# usbmidi2cv.net
KiCad netlist of a schematic drawn in EAGLE
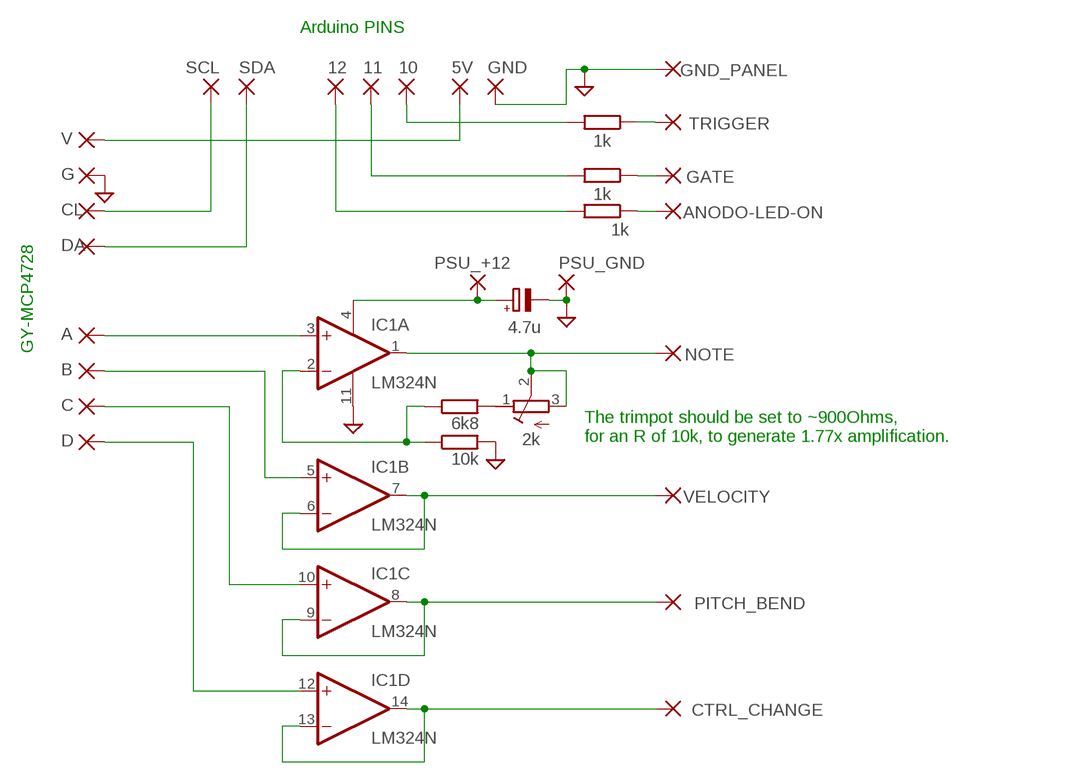
[diagram p0: schematic, sheet 1]

(export (version "E")
  (design (tool "Eeschema 10.0.6"))
  (components
    (comp (ref "5V")
      (value "1,6/0,8")
      (footprint "eagle-import:1,6_0,8")
      (libsource (lib "eagle-import") (part "1,6/0,8"))
    )
    (comp (ref "10")
      (value "1,6/0,8")
      (footprint "eagle-import:1,6_0,8")
      (libsource (lib "eagle-import") (part "1,6/0,8"))
    )
    (comp (ref "11")
      (value "1,6/0,8")
      (footprint "eagle-import:1,6_0,8")
      (libsource (lib "eagle-import") (part "1,6/0,8"))
    )
    (comp (ref "12")
      (value "1,6/0,8")
      (footprint "eagle-import:1,6_0,8")
      (libsource (lib "eagle-import") (part "1,6/0,8"))
    )
    (comp (ref "A")
      (value "1,6/0,8")
      (footprint "eagle-import:1,6_0,8")
      (libsource (lib "eagle-import") (part "1,6/0,8"))
    )
    (comp (ref "ANODO-LED-ON")
      (value "1,6/0,8")
      (footprint "eagle-import:1,6_0,8")
      (libsource (lib "eagle-import") (part "1,6/0,8"))
    )
    (comp (ref "B")
      (value "1,6/0,8")
      (footprint "eagle-import:1,6_0,8")
      (libsource (lib "eagle-import") (part "1,6/0,8"))
    )
    (comp (ref "C")
      (value "1,6/0,8")
      (footprint "eagle-import:1,6_0,8")
      (libsource (lib "eagle-import") (part "1,6/0,8"))
    )
    (comp (ref "C1")
      (value "4.7u")
      (footprint "eagle-import:E2,5-6")
      (libsource (lib "eagle-import") (part "CPOL-EUE2.5-6"))
    )
    (comp (ref "CL")
      (value "1,6/0,8")
      (footprint "eagle-import:1,6_0,8")
      (libsource (lib "eagle-import") (part "1,6/0,8"))
    )
    (comp (ref "CTRL_CHANGE")
      (value "1,6/0,8")
      (footprint "eagle-import:1,6_0,8")
      (libsource (lib "eagle-import") (part "1,6/0,8"))
    )
    (comp (ref "D")
      (value "1,6/0,8")
      (footprint "eagle-import:1,6_0,8")
      (libsource (lib "eagle-import") (part "1,6/0,8"))
    )
    (comp (ref "DA")
      (value "1,6/0,8")
      (footprint "eagle-import:1,6_0,8")
      (libsource (lib "eagle-import") (part "1,6/0,8"))
    )
    (comp (ref "G")
      (value "1,6/0,8")
      (footprint "eagle-import:1,6_0,8")
      (libsource (lib "eagle-import") (part "1,6/0,8"))
    )
    (comp (ref "GATE")
      (value "1,6/0,8")
      (footprint "eagle-import:1,6_0,8")
      (libsource (lib "eagle-import") (part "1,6/0,8"))
    )
    (comp (ref "GND")
      (value "1,6/0,8")
      (footprint "eagle-import:1,6_0,8")
      (libsource (lib "eagle-import") (part "1,6/0,8"))
    )
    (comp (ref "GND_PANEL")
      (value "1,6/0,8")
      (footprint "eagle-import:1,6_0,8")
      (libsource (lib "eagle-import") (part "1,6/0,8"))
    )
    (comp (ref "IC1")
      (value "LM324N")
      (footprint "eagle-import:DIL14")
      (libsource (lib "eagle-import") (part "LM324N"))
    )
    (comp (ref "NOTE")
      (value "1,6/0,8")
      (footprint "eagle-import:1,6_0,8")
      (libsource (lib "eagle-import") (part "1,6/0,8"))
    )
    (comp (ref "PITCH_BEND")
      (value "1,6/0,8")
      (footprint "eagle-import:1,6_0,8")
      (libsource (lib "eagle-import") (part "1,6/0,8"))
    )
    (comp (ref "PSU_+12")
      (value "1,6/0,8")
      (footprint "eagle-import:1,6_0,8")
      (libsource (lib "eagle-import") (part "1,6/0,8"))
    )
    (comp (ref "PSU_GND")
      (value "1,6/0,8")
      (footprint "eagle-import:1,6_0,8")
      (libsource (lib "eagle-import") (part "1,6/0,8"))
    )
    (comp (ref "R1")
      (value "1k")
      (footprint "eagle-import:0204_7")
      (libsource (lib "eagle-import") (part "R-EU_0204/7"))
    )
    (comp (ref "R2")
      (value "1k")
      (footprint "eagle-import:0204_7")
      (libsource (lib "eagle-import") (part "R-EU_0204/7"))
    )
    (comp (ref "R3")
      (value "1k")
      (footprint "eagle-import:0204_7")
      (libsource (lib "eagle-import") (part "R-EU_0204/7"))
    )
    (comp (ref "R4")
      (value "10k")
      (footprint "eagle-import:0207_12")
      (libsource (lib "eagle-import") (part "R-EU_0207/12"))
    )
    (comp (ref "R5")
      (value "2k")
      (footprint "eagle-import:RTRIM3006P")
      (libsource (lib "eagle-import") (part "R-TRIMM3006P"))
    )
    (comp (ref "R6")
      (value "6k8")
      (footprint "eagle-import:0207_12")
      (libsource (lib "eagle-import") (part "R-EU_0207/12"))
    )
    (comp (ref "SCL")
      (value "1,6/0,8")
      (footprint "eagle-import:1,6_0,8")
      (libsource (lib "eagle-import") (part "1,6/0,8"))
    )
    (comp (ref "SDA")
      (value "1,6/0,8")
      (footprint "eagle-import:1,6_0,8")
      (libsource (lib "eagle-import") (part "1,6/0,8"))
    )
    (comp (ref "TRIGGER")
      (value "1,6/0,8")
      (footprint "eagle-import:1,6_0,8")
      (libsource (lib "eagle-import") (part "1,6/0,8"))
    )
    (comp (ref "V")
      (value "1,6/0,8")
      (footprint "eagle-import:1,6_0,8")
      (libsource (lib "eagle-import") (part "1,6/0,8"))
    )
    (comp (ref "VELOCITY")
      (value "1,6/0,8")
      (footprint "eagle-import:1,6_0,8")
      (libsource (lib "eagle-import") (part "1,6/0,8"))
    )
  )
  (nets
    (net (code "1") (name "GND") (class "Default")
      (node (ref "C1") (pin "-") (pinfunction "-_-") (pintype "passive"))
      (node (ref "G") (pin "1") (pinfunction "P_1") (pintype "passive"))
      (node (ref "GND") (pin "1") (pinfunction "P_1") (pintype "passive"))
      (node (ref "GND_PANEL") (pin "1") (pinfunction "P_1") (pintype "passive"))
      (node (ref "IC1") (pin "11") (pinfunction "V-_11") (pintype "power_in"))
      (node (ref "PSU_GND") (pin "1") (pinfunction "P_1") (pintype "passive"))
      (node (ref "R4") (pin "2") (pinfunction "2_2") (pintype "passive"))
    )
    (net (code "2") (name "Net-(5V-P)") (class "Default")
      (node (ref "5V") (pin "1") (pinfunction "P_1") (pintype "passive"))
      (node (ref "V") (pin "1") (pinfunction "P_1") (pintype "passive"))
    )
    (net (code "3") (name "Net-(10-P)") (class "Default")
      (node (ref "10") (pin "1") (pinfunction "P_1") (pintype "passive"))
      (node (ref "R2") (pin "2") (pinfunction "2_2") (pintype "passive"))
    )
    (net (code "4") (name "Net-(11-P)") (class "Default")
      (node (ref "11") (pin "1") (pinfunction "P_1") (pintype "passive"))
      (node (ref "R1") (pin "2") (pinfunction "2_2") (pintype "passive"))
    )
    (net (code "5") (name "Net-(12-P)") (class "Default")
      (node (ref "12") (pin "1") (pinfunction "P_1") (pintype "passive"))
      (node (ref "R3") (pin "2") (pinfunction "2_2") (pintype "passive"))
    )
    (net (code "6") (name "Net-(A-P)") (class "Default")
      (node (ref "A") (pin "1") (pinfunction "P_1") (pintype "passive"))
      (node (ref "IC1") (pin "3") (pinfunction "+IN_3") (pintype "input"))
    )
    (net (code "7") (name "Net-(ANODO-LED-ON-P)") (class "Default")
      (node (ref "ANODO-LED-ON") (pin "1") (pinfunction "P_1") (pintype "passive"))
      (node (ref "R3") (pin "1") (pinfunction "1_1") (pintype "passive"))
    )
    (net (code "8") (name "Net-(B-P)") (class "Default")
      (node (ref "B") (pin "1") (pinfunction "P_1") (pintype "passive"))
      (node (ref "IC1") (pin "5") (pinfunction "+IN_5") (pintype "input"))
    )
    (net (code "9") (name "Net-(C-P)") (class "Default")
      (node (ref "C") (pin "1") (pinfunction "P_1") (pintype "passive"))
      (node (ref "IC1") (pin "10") (pinfunction "+IN_10") (pintype "input"))
    )
    (net (code "10") (name "Net-(CL-P)") (class "Default")
      (node (ref "CL") (pin "1") (pinfunction "P_1") (pintype "passive"))
      (node (ref "SCL") (pin "1") (pinfunction "P_1") (pintype "passive"))
    )
    (net (code "11") (name "Net-(CTRL_CHANGE-P)") (class "Default")
      (node (ref "CTRL_CHANGE") (pin "1") (pinfunction "P_1") (pintype "passive"))
      (node (ref "IC1") (pin "13") (pinfunction "-IN_13") (pintype "input"))
      (node (ref "IC1") (pin "14") (pinfunction "OUT_14") (pintype "output"))
    )
    (net (code "12") (name "Net-(D-P)") (class "Default")
      (node (ref "D") (pin "1") (pinfunction "P_1") (pintype "passive"))
      (node (ref "IC1") (pin "12") (pinfunction "+IN_12") (pintype "input"))
    )
    (net (code "13") (name "Net-(DA-P)") (class "Default")
      (node (ref "DA") (pin "1") (pinfunction "P_1") (pintype "passive"))
      (node (ref "SDA") (pin "1") (pinfunction "P_1") (pintype "passive"))
    )
    (net (code "14") (name "Net-(GATE-P)") (class "Default")
      (node (ref "GATE") (pin "1") (pinfunction "P_1") (pintype "passive"))
      (node (ref "R1") (pin "1") (pinfunction "1_1") (pintype "passive"))
    )
    (net (code "15") (name "Net-(IC1A--IN)") (class "Default")
      (node (ref "IC1") (pin "2") (pinfunction "-IN_2") (pintype "input"))
      (node (ref "R4") (pin "1") (pinfunction "1_1") (pintype "passive"))
      (node (ref "R6") (pin "1") (pinfunction "1_1") (pintype "passive"))
    )
    (net (code "16") (name "Net-(IC1A-OUT)") (class "Default")
      (node (ref "IC1") (pin "1") (pinfunction "OUT_1") (pintype "output"))
      (node (ref "NOTE") (pin "1") (pinfunction "P_1") (pintype "passive"))
      (node (ref "R5") (pin "2") (pinfunction "S_2") (pintype "passive"))
      (node (ref "R5") (pin "3") (pinfunction "A_3") (pintype "passive"))
    )
    (net (code "17") (name "Net-(IC1B--IN)") (class "Default")
      (node (ref "IC1") (pin "6") (pinfunction "-IN_6") (pintype "input"))
      (node (ref "IC1") (pin "7") (pinfunction "OUT_7") (pintype "output"))
      (node (ref "VELOCITY") (pin "1") (pinfunction "P_1") (pintype "passive"))
    )
    (net (code "18") (name "Net-(IC1C--IN)") (class "Default")
      (node (ref "IC1") (pin "8") (pinfunction "OUT_8") (pintype "output"))
      (node (ref "IC1") (pin "9") (pinfunction "-IN_9") (pintype "input"))
      (node (ref "PITCH_BEND") (pin "1") (pinfunction "P_1") (pintype "passive"))
    )
    (net (code "19") (name "Net-(IC1E-V+)") (class "Default")
      (node (ref "C1") (pin "+") (pinfunction "+_+") (pintype "passive"))
      (node (ref "IC1") (pin "4") (pinfunction "V+_4") (pintype "power_in"))
      (node (ref "PSU_+12") (pin "1") (pinfunction "P_1") (pintype "passive"))
    )
    (net (code "20") (name "Net-(R5-E)") (class "Default")
      (node (ref "R5") (pin "1") (pinfunction "E_1") (pintype "passive"))
      (node (ref "R6") (pin "2") (pinfunction "2_2") (pintype "passive"))
    )
    (net (code "21") (name "Net-(TRIGGER-P)") (class "Default")
      (node (ref "R2") (pin "1") (pinfunction "1_1") (pintype "passive"))
      (node (ref "TRIGGER") (pin "1") (pinfunction "P_1") (pintype "passive"))
    )
  )
)
